# Sheet1.net
KiCad netlist of a schematic drawn in Altium Designer
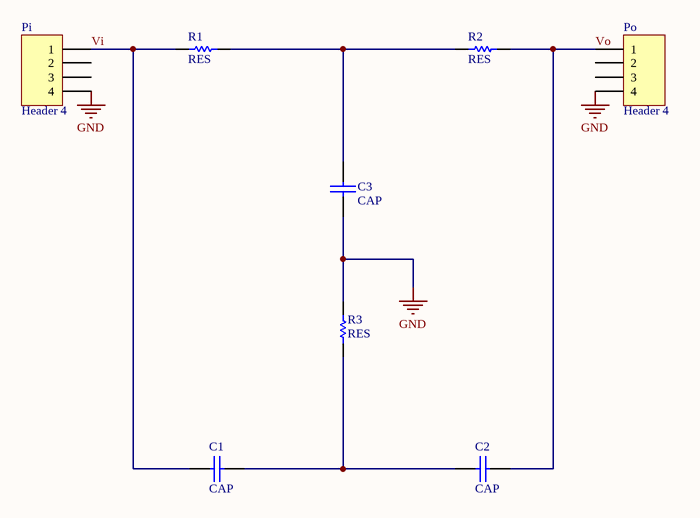
[diagram p0: Sheet1.SchDoc]

(export (version "E")
  (design (tool "Eeschema 10.0.6"))
  (components
    (comp (ref "C1") (value "CAP") (footprint "CAP100") (libsource (lib "LIBEBAL") (part "CAP")))
    (comp (ref "C2") (value "CAP") (footprint "CAP100") (libsource (lib "LIBEBAL") (part "CAP")))
    (comp (ref "C3") (value "CAP") (footprint "CAP100") (libsource (lib "LIBEBAL") (part "CAP")))
    (comp (ref "Pi")
      (value "Header 4")
      (footprint "HDR1X4")
      (description "Header, 4-Pin")
      (fields (field (name "PUBLISHER") "Altium Limited"))
      (libsource (lib "Miscellaneous Connectors") (part "Header 4"))
    )
    (comp (ref "Po")
      (value "Header 4")
      (footprint "HDR1X4")
      (description "Header, 4-Pin")
      (fields (field (name "PUBLISHER") "Altium Limited"))
      (libsource (lib "") (part "Header 4_1"))
    )
    (comp (ref "R1") (value "RES") (footprint "RES400") (libsource (lib "LIBEBAL") (part "RES")))
    (comp (ref "R2") (value "RES") (footprint "RES400") (libsource (lib "LIBEBAL") (part "RES")))
    (comp (ref "R3") (value "RES") (footprint "RES400") (libsource (lib "LIBEBAL") (part "RES")))
  )
  (nets
    (net (code "1") (name "/Vi") (class "Default")
      (node (ref "C1") (pin "1") (pinfunction "1_1") (pintype "passive"))
      (node (ref "Pi") (pin "1") (pinfunction "1_1") (pintype "passive"))
      (node (ref "R1") (pin "1") (pinfunction "1_1") (pintype "passive"))
    )
    (net (code "2") (name "/Vo") (class "Default")
      (node (ref "C2") (pin "2") (pinfunction "2_2") (pintype "passive"))
      (node (ref "Po") (pin "1") (pinfunction "1_1") (pintype "passive"))
      (node (ref "R2") (pin "2") (pinfunction "2_2") (pintype "passive"))
    )
    (net (code "3") (name "GND") (class "Default")
      (node (ref "C3") (pin "2") (pinfunction "2_2") (pintype "passive"))
      (node (ref "Pi") (pin "4") (pinfunction "4_4") (pintype "passive"))
      (node (ref "Po") (pin "4") (pinfunction "4_4") (pintype "passive"))
      (node (ref "R3") (pin "2") (pinfunction "2_2") (pintype "passive"))
    )
    (net (code "4") (name "Net-(C1-Pad2)") (class "Default")
      (node (ref "C1") (pin "2") (pinfunction "2_2") (pintype "passive"))
      (node (ref "C2") (pin "1") (pinfunction "1_1") (pintype "passive"))
      (node (ref "R3") (pin "1") (pinfunction "1_1") (pintype "passive"))
    )
    (net (code "5") (name "Net-(C3-Pad1)") (class "Default")
      (node (ref "C3") (pin "1") (pinfunction "1_1") (pintype "passive"))
      (node (ref "R1") (pin "2") (pinfunction "2_2") (pintype "passive"))
      (node (ref "R2") (pin "1") (pinfunction "1_1") (pintype "passive"))
    )
    (net (code "6") (name "unconnected-(Pi-Pad2)") (class "Default")
      (node (ref "Pi") (pin "2") (pinfunction "2_2") (pintype "passive"))
    )
    (net (code "7") (name "unconnected-(Pi-Pad3)") (class "Default")
      (node (ref "Pi") (pin "3") (pinfunction "3_3") (pintype "passive"))
    )
    (net (code "8") (name "unconnected-(Po-Pad2)") (class "Default")
      (node (ref "Po") (pin "2") (pinfunction "2_2") (pintype "passive"))
    )
    (net (code "9") (name "unconnected-(Po-Pad3)") (class "Default")
      (node (ref "Po") (pin "3") (pinfunction "3_3") (pintype "passive"))
    )
  )
)
